# MAX86141_HEG_MINI.net
KiCad netlist of a schematic drawn in EAGLE
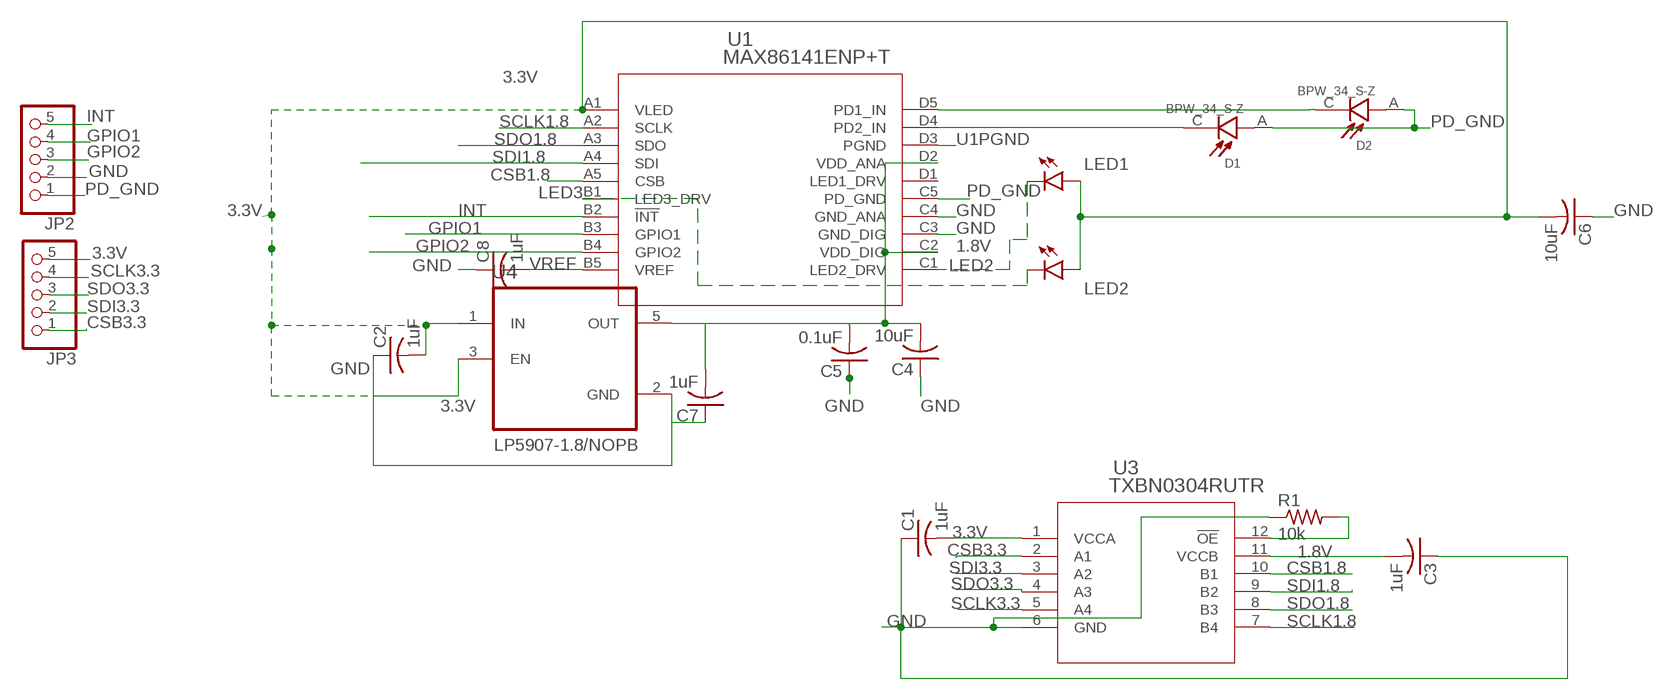
[diagram p0: schematic, sheet 1]

(export (version "E")
  (design (tool "Eeschema 10.0.6"))
  (components
    (comp (ref "C1")
      (value "1uF")
      (footprint "eagle-import:C0402")
      (libsource (lib "eagle-import") (part "C-USC0402"))
    )
    (comp (ref "C2")
      (value "1uF")
      (footprint "eagle-import:C0402")
      (libsource (lib "eagle-import") (part "C-USC0402"))
    )
    (comp (ref "C3")
      (value "1uF")
      (footprint "eagle-import:C0402")
      (libsource (lib "eagle-import") (part "C-USC0402"))
    )
    (comp (ref "C4")
      (value "10uF")
      (footprint "eagle-import:C0402")
      (libsource (lib "eagle-import") (part "C-USC0402"))
    )
    (comp (ref "C5")
      (value "0.1uF")
      (footprint "eagle-import:C0402")
      (libsource (lib "eagle-import") (part "C-USC0402"))
    )
    (comp (ref "C6")
      (value "10uF")
      (footprint "eagle-import:C0402")
      (libsource (lib "eagle-import") (part "C-USC0402"))
    )
    (comp (ref "C7")
      (value "1uF")
      (footprint "eagle-import:C0402")
      (libsource (lib "eagle-import") (part "C-USC0402"))
    )
    (comp (ref "C8")
      (value "1uF")
      (footprint "eagle-import:C0402")
      (libsource (lib "eagle-import") (part "C-USC0402"))
    )
    (comp (ref "D1")
      (value "BPW_34_S-Z")
      (footprint "eagle-import:DIO_BPW_34_S-Z")
      (fields
        (field (name "DIGI-KEY_PART_NUMBER") "475-2659-1-ND")
        (field (name "MF") "OSRAM Opto")
        (field (name "MP") "BPW 34 S-Z")
      )
      (libsource (lib "eagle-import") (part "BPW_34_S-Z"))
    )
    (comp (ref "D2")
      (value "BPW_34_S-Z")
      (footprint "eagle-import:DIO_BPW_34_S-Z")
      (fields
        (field (name "DIGI-KEY_PART_NUMBER") "475-2659-1-ND")
        (field (name "MF") "OSRAM Opto")
        (field (name "MP") "BPW 34 S-Z")
      )
      (libsource (lib "eagle-import") (part "BPW_34_S-Z"))
    )
    (comp (ref "JP2")
      (value "PINHD-1X5")
      (footprint "eagle-import:1X05")
      (libsource (lib "eagle-import") (part "PINHD-1X5"))
    )
    (comp (ref "JP3")
      (value "PINHD-1X5")
      (footprint "eagle-import:1X05")
      (libsource (lib "eagle-import") (part "PINHD-1X5"))
    )
    (comp (ref "LED1")
      (value "LEDCHIPLED_1206")
      (footprint "eagle-import:CHIPLED_1206")
      (libsource (lib "eagle-import") (part "LEDCHIPLED_1206"))
    )
    (comp (ref "LED2")
      (value "LEDCHIPLED_1206")
      (footprint "eagle-import:CHIPLED_1206")
      (libsource (lib "eagle-import") (part "LEDCHIPLED_1206"))
    )
    (comp (ref "R1")
      (value "10k")
      (footprint "eagle-import:R0402")
      (libsource (lib "eagle-import") (part "R-US_R0402"))
    )
    (comp (ref "U1")
      (value "MAX86141ENP+T")
      (footprint "eagle-import:21-100134A_20")
      (libsource (lib "eagle-import") (part "MAX86141ENP+T"))
    )
    (comp (ref "U3")
      (value "TXBN0304RUTR")
      (footprint "eagle-import:RUT12")
      (libsource (lib "eagle-import") (part "TXBN0304RUTR"))
    )
    (comp (ref "U4")
      (value "LP5907MFX-3.3/NOPB")
      (footprint "eagle-import:SOT95P280X145-5N")
      (fields (field (name "MF") "Texas Instruments"))
      (libsource (lib "eagle-import") (part "LP5907MFX-3.3/NOPB"))
    )
  )
  (nets
    (net (code "1") (name "/1.8V") (class "Default")
      (node (ref "C3") (pin "2") (pinfunction "2_2") (pintype "passive"))
      (node (ref "C4") (pin "2") (pinfunction "2_2") (pintype "passive"))
      (node (ref "C5") (pin "2") (pinfunction "2_2") (pintype "passive"))
      (node (ref "C7") (pin "2") (pinfunction "2_2") (pintype "passive"))
      (node (ref "U1") (pin "C2") (pinfunction "VDD_DIG_C2") (pintype "power_in"))
      (node (ref "U1") (pin "D2") (pinfunction "VDD_ANA_D2") (pintype "power_in"))
      (node (ref "U3") (pin "11") (pinfunction "VCCB_11") (pintype "power_in"))
      (node (ref "U4") (pin "5") (pinfunction "OUT_5") (pintype "output"))
    )
    (net (code "2") (name "/3.3V") (class "Default")
      (node (ref "C1") (pin "2") (pinfunction "2_2") (pintype "passive"))
      (node (ref "C2") (pin "2") (pinfunction "2_2") (pintype "passive"))
      (node (ref "C6") (pin "2") (pinfunction "2_2") (pintype "passive"))
      (node (ref "JP3") (pin "5") (pinfunction "5_5") (pintype "passive"))
      (node (ref "LED1") (pin "A") (pinfunction "A_A") (pintype "passive"))
      (node (ref "LED2") (pin "A") (pinfunction "A_A") (pintype "passive"))
      (node (ref "U1") (pin "A1") (pinfunction "VLED_A1") (pintype "passive"))
      (node (ref "U3") (pin "1") (pinfunction "VCCA_1") (pintype "power_in"))
      (node (ref "U4") (pin "1") (pinfunction "IN_1") (pintype "input"))
      (node (ref "U4") (pin "3") (pinfunction "EN_3") (pintype "input"))
    )
    (net (code "3") (name "/CSB1.8") (class "Default")
      (node (ref "U1") (pin "A5") (pinfunction "CSB_A5") (pintype "passive"))
      (node (ref "U3") (pin "10") (pinfunction "B1_10") (pintype "bidirectional"))
    )
    (net (code "4") (name "/CSB3.3") (class "Default")
      (node (ref "JP3") (pin "1") (pinfunction "1_1") (pintype "passive"))
      (node (ref "U3") (pin "2") (pinfunction "A1_2") (pintype "bidirectional"))
    )
    (net (code "5") (name "/GND") (class "Default")
      (node (ref "C1") (pin "1") (pinfunction "1_1") (pintype "passive"))
      (node (ref "C2") (pin "1") (pinfunction "1_1") (pintype "passive"))
      (node (ref "C3") (pin "1") (pinfunction "1_1") (pintype "passive"))
      (node (ref "C4") (pin "1") (pinfunction "1_1") (pintype "passive"))
      (node (ref "C5") (pin "1") (pinfunction "1_1") (pintype "passive"))
      (node (ref "C6") (pin "1") (pinfunction "1_1") (pintype "passive"))
      (node (ref "C7") (pin "1") (pinfunction "1_1") (pintype "passive"))
      (node (ref "C8") (pin "1") (pinfunction "1_1") (pintype "passive"))
      (node (ref "JP2") (pin "2") (pinfunction "2_2") (pintype "passive"))
      (node (ref "R1") (pin "1") (pinfunction "1_1") (pintype "passive"))
      (node (ref "U1") (pin "C3") (pinfunction "GND_DIG_C3") (pintype "passive"))
      (node (ref "U1") (pin "C4") (pinfunction "GND_ANA_C4") (pintype "passive"))
      (node (ref "U3") (pin "6") (pinfunction "GND_6") (pintype "power_in"))
      (node (ref "U4") (pin "2") (pinfunction "GND_2") (pintype "power_in"))
    )
    (net (code "6") (name "/GPIO1") (class "Default")
      (node (ref "JP2") (pin "4") (pinfunction "4_4") (pintype "passive"))
      (node (ref "U1") (pin "B3") (pinfunction "GPIO1_B3") (pintype "bidirectional"))
    )
    (net (code "7") (name "/GPIO2") (class "Default")
      (node (ref "JP2") (pin "3") (pinfunction "3_3") (pintype "passive"))
      (node (ref "U1") (pin "B4") (pinfunction "GPIO2_B4") (pintype "bidirectional"))
    )
    (net (code "8") (name "/INT") (class "Default")
      (node (ref "JP2") (pin "5") (pinfunction "5_5") (pintype "passive"))
      (node (ref "U1") (pin "B2") (pinfunction "~{INT}_B2") (pintype "passive"))
    )
    (net (code "9") (name "/LED2") (class "Default")
      (node (ref "LED1") (pin "C") (pinfunction "C_C") (pintype "passive"))
      (node (ref "U1") (pin "C1") (pinfunction "LED2_DRV_C1") (pintype "bidirectional"))
    )
    (net (code "10") (name "/LED3") (class "Default")
      (node (ref "LED2") (pin "C") (pinfunction "C_C") (pintype "passive"))
      (node (ref "U1") (pin "B1") (pinfunction "LED3_DRV_B1") (pintype "bidirectional"))
    )
    (net (code "11") (name "/PD_GND") (class "Default")
      (node (ref "D1") (pin "A") (pinfunction "A_A") (pintype "passive"))
      (node (ref "D2") (pin "A") (pinfunction "A_A") (pintype "passive"))
      (node (ref "JP2") (pin "1") (pinfunction "1_1") (pintype "passive"))
      (node (ref "U1") (pin "C5") (pinfunction "PD_GND_C5") (pintype "passive"))
    )
    (net (code "12") (name "/SCLK1.8") (class "Default")
      (node (ref "U1") (pin "A2") (pinfunction "SCLK_A2") (pintype "passive"))
      (node (ref "U3") (pin "7") (pinfunction "B4_7") (pintype "bidirectional"))
    )
    (net (code "13") (name "/SCLK3.3") (class "Default")
      (node (ref "JP3") (pin "4") (pinfunction "4_4") (pintype "passive"))
      (node (ref "U3") (pin "5") (pinfunction "A4_5") (pintype "bidirectional"))
    )
    (net (code "14") (name "/SDI1.8") (class "Default")
      (node (ref "U1") (pin "A4") (pinfunction "SDI_A4") (pintype "passive"))
      (node (ref "U3") (pin "9") (pinfunction "B2_9") (pintype "bidirectional"))
    )
    (net (code "15") (name "/SDI3.3") (class "Default")
      (node (ref "JP3") (pin "2") (pinfunction "2_2") (pintype "passive"))
      (node (ref "U3") (pin "3") (pinfunction "A2_3") (pintype "bidirectional"))
    )
    (net (code "16") (name "/SDO1.8") (class "Default")
      (node (ref "U1") (pin "A3") (pinfunction "SDO_A3") (pintype "passive"))
      (node (ref "U3") (pin "8") (pinfunction "B3_8") (pintype "bidirectional"))
    )
    (net (code "17") (name "/SDO3.3") (class "Default")
      (node (ref "JP3") (pin "3") (pinfunction "3_3") (pintype "passive"))
      (node (ref "U3") (pin "4") (pinfunction "A3_4") (pintype "bidirectional"))
    )
    (net (code "18") (name "/U1PGND") (class "Default")
      (node (ref "U1") (pin "D3") (pinfunction "PGND_D3") (pintype "passive"))
    )
    (net (code "19") (name "/VREF") (class "Default")
      (node (ref "C8") (pin "2") (pinfunction "2_2") (pintype "passive"))
      (node (ref "U1") (pin "B5") (pinfunction "VREF_B5") (pintype "power_in"))
    )
    (net (code "20") (name "Net-(U1-PD1_IN)") (class "Default")
      (node (ref "D2") (pin "C") (pinfunction "C_C") (pintype "passive"))
      (node (ref "U1") (pin "D5") (pinfunction "PD1_IN_D5") (pintype "bidirectional"))
    )
    (net (code "21") (name "Net-(U1-PD2_IN)") (class "Default")
      (node (ref "D1") (pin "C") (pinfunction "C_C") (pintype "passive"))
      (node (ref "U1") (pin "D4") (pinfunction "PD2_IN_D4") (pintype "bidirectional"))
    )
    (net (code "22") (name "Net-(U3-~{OE})") (class "Default")
      (node (ref "R1") (pin "2") (pinfunction "2_2") (pintype "passive"))
      (node (ref "U3") (pin "12") (pinfunction "~{OE}_12") (pintype "input"))
    )
    (net (code "23") (name "unconnected-(U1-LED1_DRV-PadD1)") (class "Default")
      (node (ref "U1") (pin "D1") (pinfunction "LED1_DRV_D1") (pintype "bidirectional"))
    )
  )
)
